# Sh3_Power.net
KiCad netlist of a schematic drawn in Altium Designer
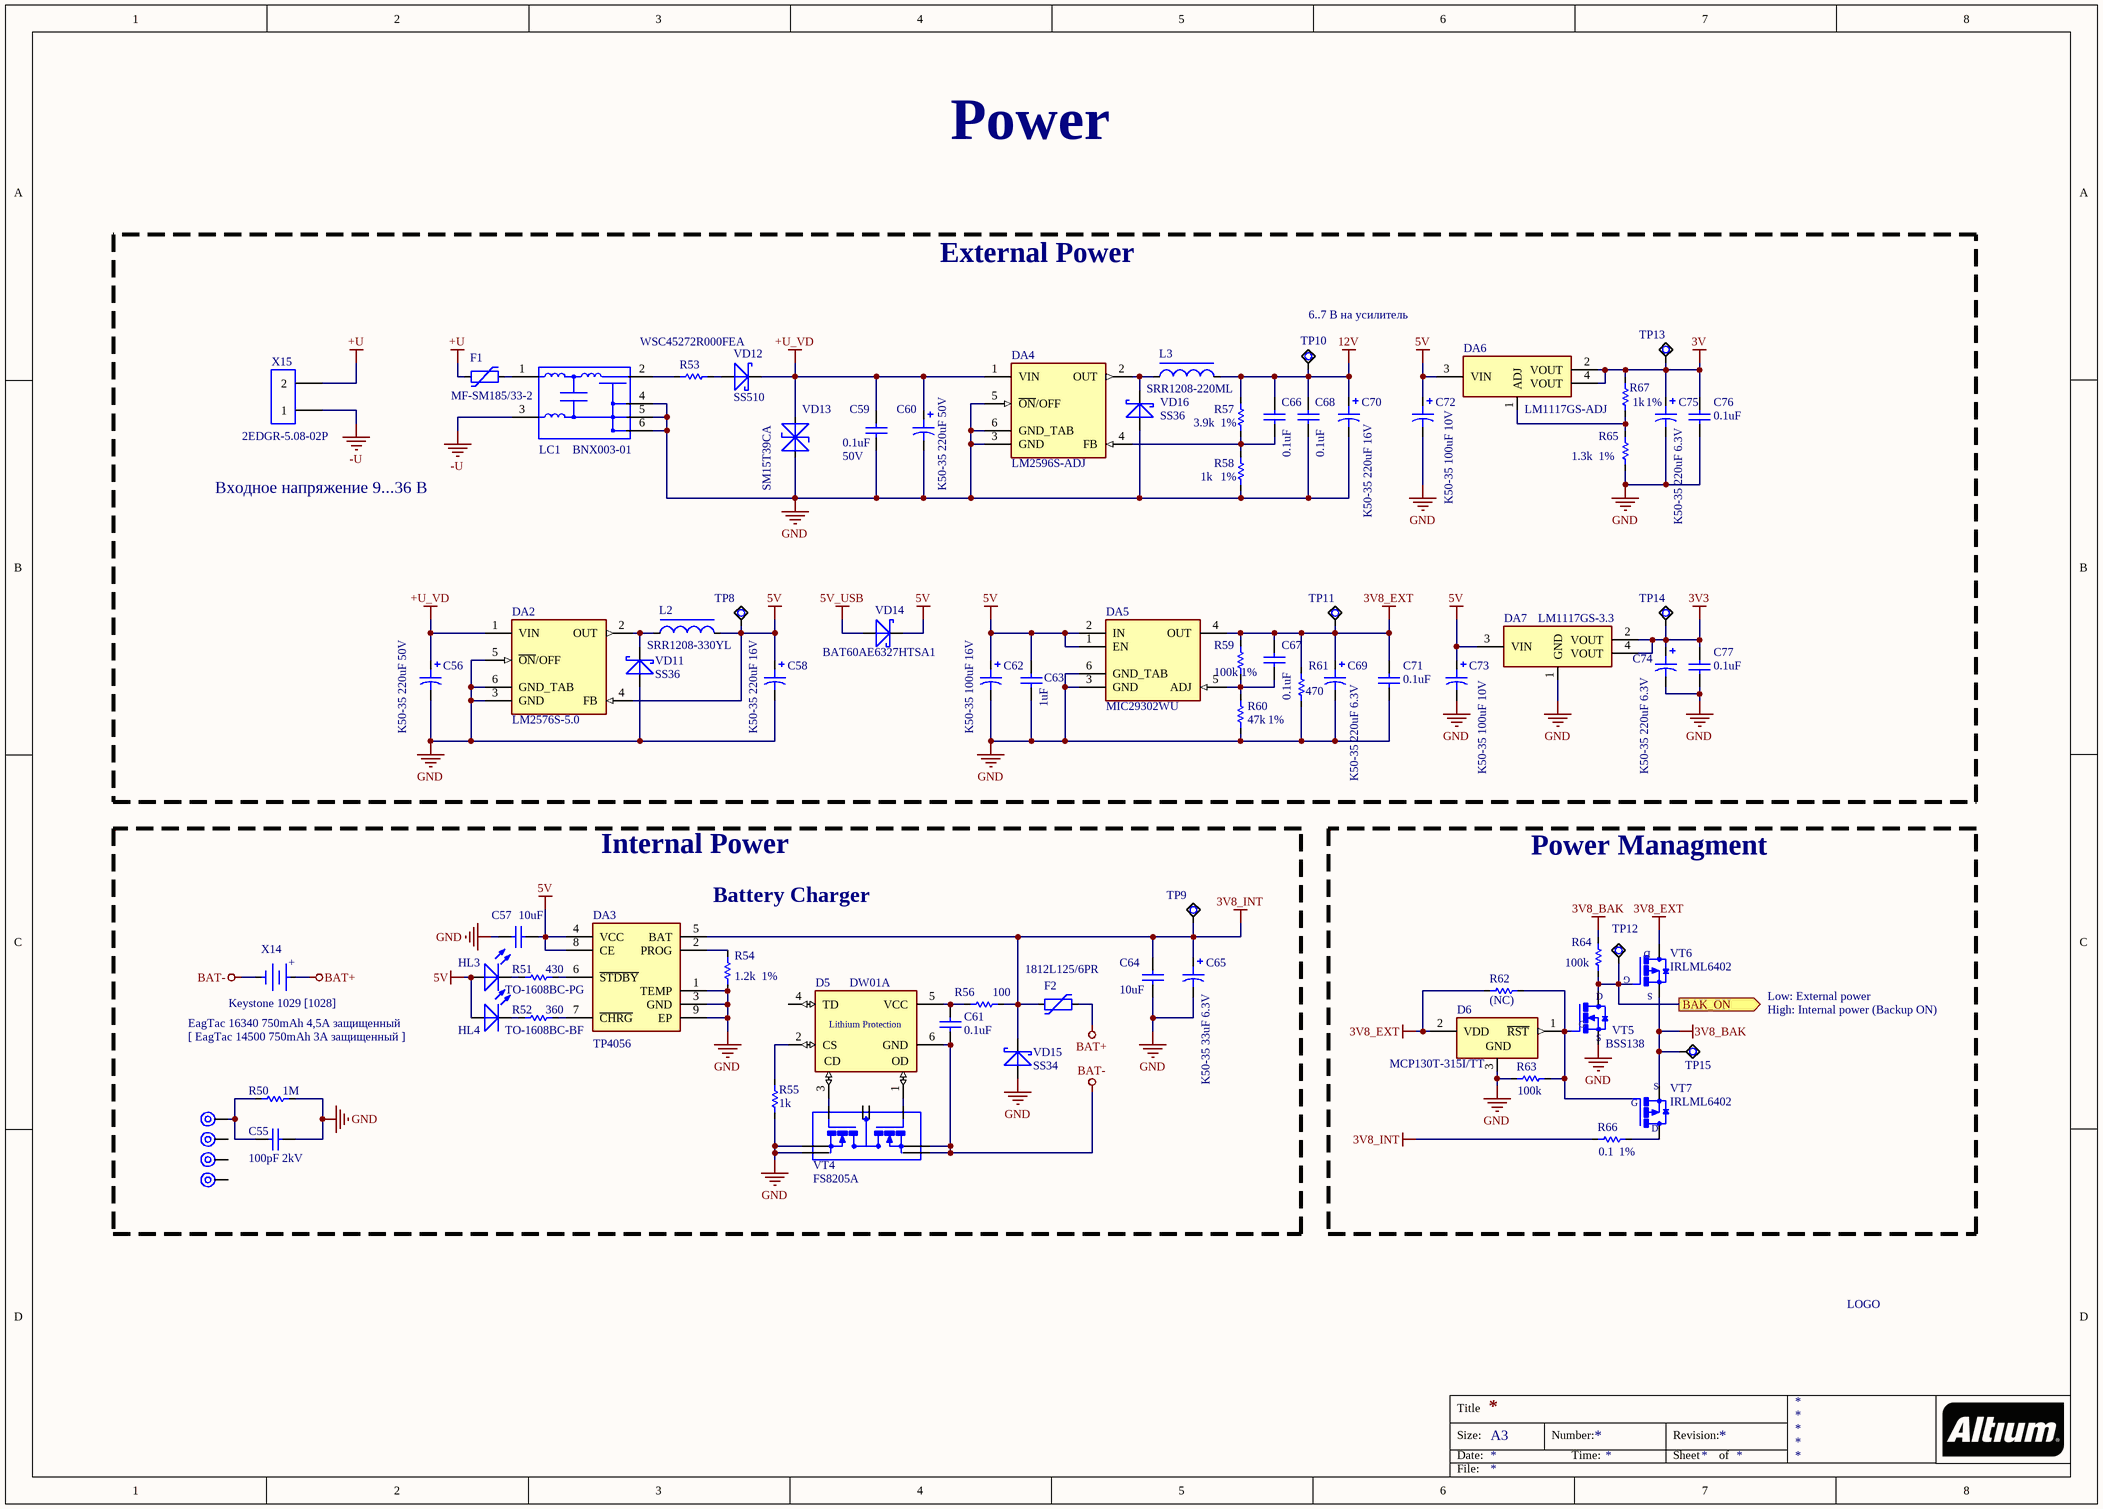
[diagram p0: Sh3_Power.SchDoc]

(export (version "E")
  (design (tool "Eeschema 10.0.6"))
  (components
    (comp (ref "BC1")
      (value "Mounting Hole")
      (footprint "body_connection_1")
      (libsource (lib "MyCompLib") (part "BodyConnector"))
    )
    (comp (ref "BC2")
      (value "Mounting Hole")
      (footprint "body_connection_1")
      (libsource (lib "MyCompLib") (part "BodyConnector"))
    )
    (comp (ref "BC3")
      (value "Mounting Hole")
      (footprint "body_connection_1")
      (libsource (lib "MyCompLib") (part "BodyConnector"))
    )
    (comp (ref "BC4")
      (value "Mounting Hole")
      (footprint "body_connection_1")
      (libsource (lib "MyCompLib") (part "BodyConnector"))
    )
    (comp (ref "C55")
      (value "100pF 2kV")
      (footprint "C_SMD1206")
      (description "1206 SMD Capacitor")
      (libsource (lib "MyCompLib") (part "C_SMD"))
    )
    (comp (ref "C56")
      (value "K50-35 220uF 50V")
      (footprint "K50-35 10x12.5x5")
      (description "Конденсатор электролитический алюминиевый")
      (libsource (lib "MyCompLib") (part "K50-35"))
    )
    (comp (ref "C57")
      (value "10uF")
      (footprint "C_SMD0603")
      (description "0603 SMD Capacitor")
      (libsource (lib "MyCompLib") (part "C_SMD"))
    )
    (comp (ref "C58")
      (value "K50-35 220uF 16V")
      (footprint "K50-35 6.3x11x2.5")
      (description "Конденсатор электролитический алюминиевый")
      (libsource (lib "MyCompLib") (part "K50-35"))
    )
    (comp (ref "C59")
      (value "0.1uF")
      (footprint "C_SMD0603")
      (description "0603 SMD Capacitor")
      (libsource (lib "MyCompLib") (part "C_SMD"))
    )
    (comp (ref "C60")
      (value "K50-35 220uF 50V")
      (footprint "K50-35 10x12.5x5")
      (description "Конденсатор электролитический алюминиевый")
      (libsource (lib "MyCompLib") (part "K50-35"))
    )
    (comp (ref "C61")
      (value "0.1uF")
      (footprint "C_SMD0603")
      (description "0603 SMD Capacitor")
      (libsource (lib "MyCompLib") (part "C_SMD"))
    )
    (comp (ref "C62")
      (value "K50-35 100uF 16V")
      (footprint "K50-35 6.3x11x2.5")
      (description "Конденсатор электролитический алюминиевый")
      (libsource (lib "MyCompLib") (part "K50-35"))
    )
    (comp (ref "C63")
      (value "1uF")
      (footprint "C_SMD0603")
      (description "0603 SMD Capacitor")
      (libsource (lib "MyCompLib") (part "C_SMD"))
    )
    (comp (ref "C64")
      (value "10uF")
      (footprint "C_SMD0603")
      (description "0603 SMD Capacitor")
      (libsource (lib "MyCompLib") (part "C_SMD"))
    )
    (comp (ref "C65")
      (value "K50-35 33uF 6.3V")
      (footprint "K50-35mini 4x7x2")
      (description "Конденсатор электролитический алюминиевый")
      (libsource (lib "MyCompLib") (part "K50-35"))
    )
    (comp (ref "C66")
      (value "0.1uF")
      (footprint "C_SMD0603")
      (description "0603 SMD Capacitor")
      (libsource (lib "MyCompLib") (part "C_SMD"))
    )
    (comp (ref "C67")
      (value "0.1uF")
      (footprint "C_SMD0603")
      (description "0603 SMD Capacitor")
      (libsource (lib "MyCompLib") (part "C_SMD"))
    )
    (comp (ref "C68")
      (value "0.1uF")
      (footprint "C_SMD0603")
      (description "0603 SMD Capacitor")
      (libsource (lib "MyCompLib") (part "C_SMD"))
    )
    (comp (ref "C69")
      (value "K50-35 220uF 6.3V")
      (footprint "K50-35 6.3x11x2.5")
      (description "Конденсатор электролитический алюминиевый")
      (libsource (lib "MyCompLib") (part "K50-35"))
    )
    (comp (ref "C70")
      (value "K50-35 220uF 16V")
      (footprint "K50-35 6.3x11x2.5")
      (description "Конденсатор электролитический алюминиевый")
      (libsource (lib "MyCompLib") (part "K50-35"))
    )
    (comp (ref "C71")
      (value "0.1uF")
      (footprint "C_SMD0603")
      (description "0603 SMD Capacitor")
      (libsource (lib "MyCompLib") (part "C_SMD"))
    )
    (comp (ref "C72")
      (value "K50-35 100uF 10V")
      (footprint "K50-35 5x11x2")
      (description "Конденсатор электролитический алюминиевый")
      (libsource (lib "MyCompLib") (part "K50-35"))
    )
    (comp (ref "C73")
      (value "K50-35 100uF 10V")
      (footprint "K50-35 5x11x2")
      (description "Конденсатор электролитический алюминиевый")
      (libsource (lib "MyCompLib") (part "K50-35"))
    )
    (comp (ref "C74")
      (value "K50-35 220uF 6.3V")
      (footprint "K50-35 6.3x11x2.5")
      (description "Конденсатор электролитический алюминиевый")
      (libsource (lib "MyCompLib") (part "K50-35"))
    )
    (comp (ref "C75")
      (value "K50-35 220uF 6.3V")
      (footprint "K50-35 6.3x11x2.5")
      (description "Конденсатор электролитический алюминиевый")
      (libsource (lib "MyCompLib") (part "K50-35"))
    )
    (comp (ref "C76")
      (value "0.1uF")
      (footprint "C_SMD0603")
      (description "0603 SMD Capacitor")
      (libsource (lib "MyCompLib") (part "C_SMD"))
    )
    (comp (ref "C77")
      (value "0.1uF")
      (footprint "C_SMD0603")
      (description "0603 SMD Capacitor")
      (libsource (lib "MyCompLib") (part "C_SMD"))
    )
    (comp (ref "D5")
      (value "DW01A")
      (footprint "SOT23-6-D")
      (description "Pushbutton Switch SPST-NC Standard Panel Mount, Front")
      (fields (field (name "MF") "Fortune Semiconductor"))
      (libsource (lib "MyCompLib") (part "DW01A"))
    )
    (comp (ref "D6")
      (value "MCP130T-315I/TT")
      (footprint "SOT23-3")
      (description "3.15 V 150 ms Microcontroller Supervisory Circuit - SOT-23-3")
      (fields (field (name "MF") "Microchip"))
      (libsource (lib "MyCompLib") (part "MCP130T-315I/TT"))
    )
    (comp (ref "DA2")
      (value "LM2576S-5.0")
      (footprint "TO263-5")
      (description "Импульсный понижающий регулятор напряжения, 5В, 3А, [TO-263]")
      (libsource (lib "MyCompLib") (part "LM2576S"))
    )
    (comp (ref "DA3")
      (value "TP4056")
      (footprint "SOIC127P600X175-9N")
      (description "Li-lon Battery Charger  1A Standalone Linear with Thermal Regulation in SOP-8")
      (libsource (lib "MyCompLib") (part "TP4056"))
    )
    (comp (ref "DA4")
      (value "LM2596S-ADJ")
      (footprint "TO263-5")
      (description "SIMPLE SWITCHER&#174; 4.5V to 40V, 3A Low Component Count Step-Down Regulator")
      (libsource (lib "MyCompLib") (part "LM2596S"))
    )
    (comp (ref "DA5")
      (value "MIC29302WU")
      (footprint "TO263-5 - heatsink")
      (libsource (lib "MyCompLib") (part "MIC29302WU"))
    )
    (comp (ref "DA6")
      (value "LM1117GS-ADJ")
      (footprint "SOT223")
      (libsource (lib "MyCompLib") (part "LM1117GS-ADJ"))
    )
    (comp (ref "DA7")
      (value "LM1117GS-3.3")
      (footprint "SOT223")
      (libsource (lib "MyCompLib") (part "LM1117GS-3.3"))
    )
    (comp (ref "F1")
      (value "MF-SM185/33-2")
      (footprint "FUSM8867X300N")
      (libsource (lib "MyCompLib") (part "MF-SM185/33-2"))
    )
    (comp (ref "F2")
      (value "1812L125/6PR")
      (footprint "FUSSC324X455X62L")
      (description "Предохранитель SMD 6 VDC 2.5 A")
      (libsource (lib "MyCompLib") (part "1812L125/6PR"))
    )
    (comp (ref "HL3")
      (value "TO-1608BC-PG")
      (footprint "LED_SMD1608GREEN")
      (description "Vf =2 V, 20mA, 0603\r\n\r\nTO-1608BC-BF \\  TO-1608BC-MRE")
      (libsource (lib "MyCompLib") (part "LED_SMD"))
    )
    (comp (ref "HL4")
      (value "TO-1608BC-BF")
      (footprint "LED_SMD1608")
      (description "Vf =2 V, 20mA, 0603\r\n\r\nTO-1608BC-BF \\  TO-1608BC-MRE")
      (libsource (lib "MyCompLib") (part "LED_SMD"))
    )
    (comp (ref "L2")
      (value "SRR1208-330YL")
      (footprint "SRR1208")
      (libsource (lib "MyCompLib") (part "SRR1208-330YL"))
    )
    (comp (ref "L3")
      (value "SRR1208-220ML")
      (footprint "SRR1208")
      (libsource (lib "MyCompLib") (part "SRR1208-330YL"))
    )
    (comp (ref "LC1")
      (value "BNX003-01")
      (footprint "Murata_BNX_L12MM5_W11MM5_T13MM0_MFG")
      (description "EMI фильтр индуктивно-емкостной 10A 150VDC 40дБ")
      (libsource (lib "MyCompLib") (part "BNX003-01"))
    )
    (comp (ref "N1")
      (value "Logo")
      (footprint "LOGO_SS")
      (description "Print on PCB mask")
      (libsource (lib "MyCompLib") (part "Logo"))
    )
    (comp (ref "R50")
      (value "1M")
      (footprint "R_SMD1206")
      (description "1206 SMD Resistor")
      (libsource (lib "MyCompLib") (part "R_SMD"))
    )
    (comp (ref "R51")
      (value "430")
      (footprint "R_SMD0603")
      (description "0603 SMD Resistor")
      (libsource (lib "MyCompLib") (part "R_SMD"))
    )
    (comp (ref "R52")
      (value "360")
      (footprint "R_SMD0603")
      (description "0603 SMD Resistor")
      (libsource (lib "MyCompLib") (part "R_SMD"))
    )
    (comp (ref "R53")
      (value "WSC45272R000FEA")
      (footprint "R_SMD4527")
      (description "SMD чип резистор, с проволочной обмоткой, 4527, 2 Ом, Серия WSC, 2 Вт")
      (libsource (lib "MyCompLib") (part "WSC45272R000FEA"))
    )
    (comp (ref "R54")
      (value "1.2k")
      (footprint "R_SMD0603")
      (description "0603 SMD Resistor 1%")
      (libsource (lib "MyCompLib") (part "R_SMD"))
    )
    (comp (ref "R55")
      (value "1k")
      (footprint "R_SMD0603")
      (description "0603 SMD Resistor")
      (libsource (lib "MyCompLib") (part "R_SMD"))
    )
    (comp (ref "R56")
      (value "100")
      (footprint "R_SMD0603")
      (description "0603 SMD Resistor")
      (libsource (lib "MyCompLib") (part "R_SMD"))
    )
    (comp (ref "R57")
      (value "3.9k")
      (footprint "R_SMD0603")
      (description "0603 SMD Resistor 1%")
      (libsource (lib "MyCompLib") (part "R_SMD"))
    )
    (comp (ref "R58")
      (value "1k")
      (footprint "R_SMD0603")
      (description "0603 SMD Resistor 1%")
      (libsource (lib "MyCompLib") (part "R_SMD"))
    )
    (comp (ref "R59")
      (value "100k")
      (footprint "R_SMD0603")
      (description "0603 SMD Resistor 1%")
      (libsource (lib "MyCompLib") (part "R_SMD"))
    )
    (comp (ref "R60")
      (value "47k")
      (footprint "R_SMD0603")
      (description "0603 SMD Resistor 1%")
      (libsource (lib "MyCompLib") (part "R_SMD"))
    )
    (comp (ref "R61")
      (value "470")
      (footprint "R_SMD0805")
      (description "0805 SMD Resistor")
      (libsource (lib "MyCompLib") (part "R_SMD"))
    )
    (comp (ref "R62")
      (value "(NC)")
      (footprint "R_SMD0603")
      (description "0603 SMD Resistor")
      (libsource (lib "MyCompLib") (part "R_SMD"))
    )
    (comp (ref "R63")
      (value "100k")
      (footprint "R_SMD0603")
      (description "0603 SMD Resistor")
      (libsource (lib "MyCompLib") (part "R_SMD"))
    )
    (comp (ref "R64")
      (value "100k")
      (footprint "R_SMD0603")
      (description "0603 SMD Resistor")
      (libsource (lib "MyCompLib") (part "R_SMD"))
    )
    (comp (ref "R65")
      (value "1.3k")
      (footprint "R_SMD0603")
      (description "0603 SMD Resistor 1%")
      (libsource (lib "MyCompLib") (part "R_SMD"))
    )
    (comp (ref "R66")
      (value "0.1")
      (footprint "R_SMD0805")
      (description "0805 SMD Resistor 1%")
      (libsource (lib "MyCompLib") (part "R_SMD"))
    )
    (comp (ref "R67")
      (value "1k")
      (footprint "R_SMD0603")
      (description "0603 SMD Resistor 1%")
      (libsource (lib "MyCompLib") (part "R_SMD"))
    )
    (comp (ref "TP8")
      (value "Test_point")
      (footprint "TEST_POINT")
      (description "Test point for PCB")
      (libsource (lib "MyCompLib") (part "Test_point"))
    )
    (comp (ref "TP9")
      (value "Test_point")
      (footprint "TEST_POINT")
      (description "Test point for PCB")
      (libsource (lib "MyCompLib") (part "Test_point"))
    )
    (comp (ref "TP10")
      (value "Test_point")
      (footprint "TEST_POINT")
      (description "Test point for PCB")
      (libsource (lib "MyCompLib") (part "Test_point"))
    )
    (comp (ref "TP11")
      (value "Test_point")
      (footprint "TEST_POINT")
      (description "Test point for PCB")
      (libsource (lib "MyCompLib") (part "Test_point"))
    )
    (comp (ref "TP12")
      (value "Test_point")
      (footprint "TEST_POINT")
      (description "Test point for PCB")
      (libsource (lib "MyCompLib") (part "Test_point"))
    )
    (comp (ref "TP13")
      (value "Test_point")
      (footprint "TEST_POINT")
      (description "Test point for PCB")
      (libsource (lib "MyCompLib") (part "Test_point"))
    )
    (comp (ref "TP14")
      (value "Test_point")
      (footprint "TEST_POINT")
      (description "Test point for PCB")
      (libsource (lib "MyCompLib") (part "Test_point"))
    )
    (comp (ref "TP15")
      (value "Test_point")
      (footprint "TEST_POINT")
      (description "Test point for PCB")
      (libsource (lib "MyCompLib") (part "Test_point"))
    )
    (comp (ref "VD11")
      (value "SS36")
      (footprint "DO214AB SMC")
      (description "Schottky; DO-214AB; 3.0A IF; 0.75V; 60V; 100A IFRM; 10000V/us; 1000pF")
      (libsource (lib "MyCompLib") (part "SS36"))
    )
    (comp (ref "VD12")
      (value "SS510")
      (footprint "SMC")
      (description "Диод Шоттки 5A 100V (SMC)")
      (libsource (lib "MyCompLib") (part "SS510"))
    )
    (comp (ref "VD13")
      (value "SM15T39CA")
      (footprint "DO214AB SMC")
      (description "TVS Diode Bi-Directional SM15T39CA 69.7V, 1500W, SMC 2-Pin")
      (libsource (lib "MyCompLib") (part "SM15T39CA"))
    )
    (comp (ref "VD14")
      (value "BAT60AE6327HTSA1")
      (footprint "SOD-323")
      (description "Диод Шоттки 3А 10В [SOD-323]")
      (libsource (lib "MyCompLib") (part "BAT60AE6327HTSA1"))
    )
    (comp (ref "VD15")
      (value "SS34")
      (footprint "DO214AB SMC")
      (description "Schottky; DO-214AB; 3.0A IF; 0.75V; 40V; 100A IFRM; 10000V/us; 1000pF")
      (libsource (lib "MyCompLib") (part "SS34"))
    )
    (comp (ref "VD16")
      (value "SS36")
      (footprint "DO214AB SMC")
      (description "Schottky; DO-214AB; 3.0A IF; 0.75V; 60V; 100A IFRM; 10000V/us; 1000pF")
      (libsource (lib "MyCompLib") (part "SS36"))
    )
    (comp (ref "VT4")
      (value "FS8205A")
      (footprint "SOP65P640X120-8N")
      (description "20V 6A DUAL N-Channel MOSFET Transistor")
      (libsource (lib "MyCompLib") (part "FS8205A"))
    )
    (comp (ref "VT5")
      (value "BSS138")
      (footprint "SOT23-3")
      (description "MOSFET, N-канал, 0.2А, 50В, [SOT-23]")
      (libsource (lib "MyCompLib") (part "BSS138"))
    )
    (comp (ref "VT6")
      (value "IRLML6402")
      (footprint "SOT23")
      (description "P-Channel 20V 3.7A _Ta_ 1.3W _Ta_ Surface Mount/SOT-23")
      (fields (field (name "MF") "Infineon Technologies"))
      (libsource (lib "MyCompLib") (part "IRLML6402"))
    )
    (comp (ref "VT7")
      (value "IRLML6402")
      (footprint "SOT23")
      (description "P-Channel 20V 3.7A _Ta_ 1.3W _Ta_ Surface Mount/SOT-23")
      (fields (field (name "MF") "Infineon Technologies"))
      (libsource (lib "") (part "IRLML6402_1"))
    )
    (comp (ref "X14")
      (value "Keystone 1029 [1028]")
      (footprint "BAT_keystone1028+1029")
      (description "16340 2/3A [14500 AA] Battery Holder")
      (libsource (lib "MyCompLib") (part "Combo Battery Holder"))
    )
    (comp (ref "X15")
      (value "2EDGR-5.08-02P")
      (footprint "2EDGR-5.08-02P")
      (libsource (lib "MyCompLib") (part "2EDGR-5.08-02P"))
    )
  )
  (nets
    (net (code "1") (name "+U") (class "Default")
      (node (ref "F1") (pin "1") (pinfunction "1_1") (pintype "passive"))
      (node (ref "X15") (pin "2") (pinfunction "2_2") (pintype "passive"))
    )
    (net (code "2") (name "+U_VD") (class "Default")
      (node (ref "C56") (pin "1") (pinfunction "1_1") (pintype "passive"))
      (node (ref "C59") (pin "1") (pinfunction "1_1") (pintype "passive"))
      (node (ref "C60") (pin "1") (pinfunction "1_1") (pintype "passive"))
      (node (ref "DA2") (pin "1") (pinfunction "VIN_1") (pintype "power_in"))
      (node (ref "DA4") (pin "1") (pinfunction "VIN_1") (pintype "power_in"))
      (node (ref "VD12") (pin "C") (pinfunction "NEG_C") (pintype "passive"))
      (node (ref "VD13") (pin "2") (pinfunction "K_2") (pintype "passive"))
    )
    (net (code "3") (name "-U") (class "Default")
      (node (ref "LC1") (pin "3") (pinfunction "PSG_3") (pintype "passive"))
      (node (ref "X15") (pin "1") (pinfunction "1_1") (pintype "passive"))
    )
    (net (code "4") (name "/BAK_ON") (class "Default")
      (node (ref "R64") (pin "2") (pinfunction "CW_2") (pintype "passive"))
      (node (ref "TP12") (pin "1") (pinfunction "1_1") (pintype "passive"))
      (node (ref "VT5") (pin "3") (pinfunction "D_3") (pintype "passive"))
      (node (ref "VT6") (pin "1") (pinfunction "G_1") (pintype "passive"))
    )
    (net (code "5") (name "3V") (class "Default")
      (node (ref "C75") (pin "1") (pinfunction "1_1") (pintype "passive"))
      (node (ref "C76") (pin "1") (pinfunction "1_1") (pintype "passive"))
      (node (ref "DA6") (pin "2") (pinfunction "VOUT_2") (pintype "power_in"))
      (node (ref "DA6") (pin "4") (pinfunction "VOUT_4") (pintype "power_in"))
      (node (ref "R67") (pin "2") (pinfunction "CW_2") (pintype "passive"))
      (node (ref "TP13") (pin "1") (pinfunction "1_1") (pintype "passive"))
    )
    (net (code "6") (name "3V3") (class "Default")
      (node (ref "C74") (pin "1") (pinfunction "1_1") (pintype "passive"))
      (node (ref "C77") (pin "1") (pinfunction "1_1") (pintype "passive"))
      (node (ref "DA7") (pin "2") (pinfunction "VOUT_2") (pintype "power_in"))
      (node (ref "DA7") (pin "4") (pinfunction "VOUT_4") (pintype "power_in"))
      (node (ref "TP14") (pin "1") (pinfunction "1_1") (pintype "passive"))
    )
    (net (code "7") (name "3V8_BAK") (class "Default")
      (node (ref "R64") (pin "1") (pinfunction "CCW_1") (pintype "passive"))
      (node (ref "TP15") (pin "1") (pinfunction "1_1") (pintype "passive"))
      (node (ref "VT6") (pin "2") (pinfunction "S_2") (pintype "passive"))
      (node (ref "VT7") (pin "2") (pinfunction "S_2") (pintype "passive"))
    )
    (net (code "8") (name "3V8_EXT") (class "Default")
      (node (ref "C67") (pin "1") (pinfunction "1_1") (pintype "passive"))
      (node (ref "C69") (pin "1") (pinfunction "1_1") (pintype "passive"))
      (node (ref "C71") (pin "1") (pinfunction "1_1") (pintype "passive"))
      (node (ref "D6") (pin "2") (pinfunction "VDD_2") (pintype "power_in"))
      (node (ref "DA5") (pin "4") (pinfunction "OUT_4") (pintype "power_in"))
      (node (ref "R59") (pin "2") (pinfunction "CW_2") (pintype "passive"))
      (node (ref "R61") (pin "2") (pinfunction "CW_2") (pintype "passive"))
      (node (ref "R62") (pin "2") (pinfunction "CW_2") (pintype "passive"))
      (node (ref "TP11") (pin "1") (pinfunction "1_1") (pintype "passive"))
      (node (ref "VT6") (pin "3") (pinfunction "D_3") (pintype "passive"))
    )
    (net (code "9") (name "3V8_INT") (class "Default")
      (node (ref "C64") (pin "1") (pinfunction "1_1") (pintype "passive"))
      (node (ref "C65") (pin "1") (pinfunction "1_1") (pintype "passive"))
      (node (ref "DA3") (pin "5") (pinfunction "BAT_5") (pintype "passive"))
      (node (ref "F2") (pin "1") (pinfunction "1_1") (pintype "passive"))
      (node (ref "R56") (pin "1") (pinfunction "CCW_1") (pintype "passive"))
      (node (ref "R66") (pin "2") (pinfunction "CW_2") (pintype "passive"))
      (node (ref "TP9") (pin "1") (pinfunction "1_1") (pintype "passive"))
      (node (ref "VD15") (pin "2") (pinfunction "NEG_2") (pintype "passive"))
    )
    (net (code "10") (name "5V") (class "Default")
      (node (ref "C57") (pin "2") (pinfunction "2_2") (pintype "passive"))
      (node (ref "C58") (pin "1") (pinfunction "1_1") (pintype "passive"))
      (node (ref "C62") (pin "1") (pinfunction "1_1") (pintype "passive"))
      (node (ref "C63") (pin "1") (pinfunction "1_1") (pintype "passive"))
      (node (ref "C72") (pin "1") (pinfunction "1_1") (pintype "passive"))
      (node (ref "C73") (pin "1") (pinfunction "1_1") (pintype "passive"))
      (node (ref "DA2") (pin "4") (pinfunction "FB_4") (pintype "input"))
      (node (ref "DA3") (pin "4") (pinfunction "VCC_4") (pintype "passive"))
      (node (ref "DA3") (pin "8") (pinfunction "CE_8") (pintype "passive"))
      (node (ref "DA5") (pin "1") (pinfunction "EN_1") (pintype "power_in"))
      (node (ref "DA5") (pin "2") (pinfunction "IN_2") (pintype "power_in"))
      (node (ref "DA6") (pin "3") (pinfunction "VIN_3") (pintype "power_in"))
      (node (ref "DA7") (pin "3") (pinfunction "VIN_3") (pintype "power_in"))
      (node (ref "HL3") (pin "1") (pinfunction "POS_1") (pintype "passive"))
      (node (ref "HL4") (pin "1") (pinfunction "POS_1") (pintype "passive"))
      (node (ref "L2") (pin "2") (pinfunction "2_2") (pintype "passive"))
      (node (ref "TP8") (pin "1") (pinfunction "1_1") (pintype "passive"))
      (node (ref "VD14") (pin "2") (pinfunction "NEG_2") (pintype "passive"))
    )
    (net (code "11") (name "5V_USB") (class "Default")
      (node (ref "VD14") (pin "1") (pinfunction "POS_1") (pintype "passive"))
    )
    (net (code "12") (name "12V") (class "Default")
      (node (ref "C66") (pin "1") (pinfunction "1_1") (pintype "passive"))
      (node (ref "C68") (pin "1") (pinfunction "1_1") (pintype "passive"))
      (node (ref "C70") (pin "1") (pinfunction "1_1") (pintype "passive"))
      (node (ref "L3") (pin "2") (pinfunction "2_2") (pintype "passive"))
      (node (ref "R57") (pin "2") (pinfunction "CW_2") (pintype "passive"))
      (node (ref "TP10") (pin "1") (pinfunction "1_1") (pintype "passive"))
    )
    (net (code "13") (name "BAT+") (class "Default")
      (node (ref "F2") (pin "2") (pinfunction "2_2") (pintype "passive"))
      (node (ref "X14") (pin "POS") (pinfunction "POS_POS") (pintype "passive"))
    )
    (net (code "14") (name "BAT-") (class "Default")
      (node (ref "C61") (pin "2") (pinfunction "2_2") (pintype "passive"))
      (node (ref "D5") (pin "6") (pinfunction "GND_6") (pintype "power_in"))
      (node (ref "VT4") (pin "2") (pinfunction "S1_1_2") (pintype "passive"))
      (node (ref "VT4") (pin "3") (pinfunction "S1_2_3") (pintype "passive"))
      (node (ref "X14") (pin "NEG") (pinfunction "NEG_NEG") (pintype "passive"))
    )
    (net (code "15") (name "GND") (class "Default")
      (node (ref "C55") (pin "2") (pinfunction "2_2") (pintype "passive"))
      (node (ref "C56") (pin "2") (pinfunction "2_2") (pintype "passive"))
      (node (ref "C57") (pin "1") (pinfunction "1_1") (pintype "passive"))
      (node (ref "C58") (pin "2") (pinfunction "2_2") (pintype "passive"))
      (node (ref "C59") (pin "2") (pinfunction "2_2") (pintype "passive"))
      (node (ref "C60") (pin "2") (pinfunction "2_2") (pintype "passive"))
      (node (ref "C62") (pin "2") (pinfunction "2_2") (pintype "passive"))
      (node (ref "C63") (pin "2") (pinfunction "2_2") (pintype "passive"))
      (node (ref "C64") (pin "2") (pinfunction "2_2") (pintype "passive"))
      (node (ref "C65") (pin "2") (pinfunction "2_2") (pintype "passive"))
      (node (ref "C68") (pin "2") (pinfunction "2_2") (pintype "passive"))
      (node (ref "C69") (pin "2") (pinfunction "2_2") (pintype "passive"))
      (node (ref "C70") (pin "2") (pinfunction "2_2") (pintype "passive"))
      (node (ref "C71") (pin "2") (pinfunction "2_2") (pintype "passive"))
      (node (ref "C72") (pin "2") (pinfunction "2_2") (pintype "passive"))
      (node (ref "C73") (pin "2") (pinfunction "2_2") (pintype "passive"))
      (node (ref "C74") (pin "2") (pinfunction "2_2") (pintype "passive"))
      (node (ref "C75") (pin "2") (pinfunction "2_2") (pintype "passive"))
      (node (ref "C76") (pin "2") (pinfunction "2_2") (pintype "passive"))
      (node (ref "C77") (pin "2") (pinfunction "2_2") (pintype "passive"))
      (node (ref "D6") (pin "3") (pinfunction "VSS_3") (pintype "power_in"))
      (node (ref "DA2") (pin "3") (pinfunction "GND_3") (pintype "passive"))
      (node (ref "DA2") (pin "5") (pinfunction "~{ON}/OFF_5") (pintype "input"))
      (node (ref "DA2") (pin "6") (pinfunction "GND_TAB_6") (pintype "passive"))
      (node (ref "DA3") (pin "1") (pinfunction "TEMP_1") (pintype "passive"))
      (node (ref "DA3") (pin "3") (pinfunction "GND_3") (pintype "passive"))
      (node (ref "DA3") (pin "9") (pinfunction "EP_9") (pintype "passive"))
      (node (ref "DA4") (pin "3") (pinfunction "GND_3") (pintype "passive"))
      (node (ref "DA4") (pin "5") (pinfunction "~{ON}/OFF_5") (pintype "input"))
      (node (ref "DA4") (pin "6") (pinfunction "GND_TAB_6") (pintype "passive"))
      (node (ref "DA5") (pin "3") (pinfunction "GND_3") (pintype "passive"))
      (node (ref "DA5") (pin "6") (pinfunction "GND_TAB_6") (pintype "passive"))
      (node (ref "DA7") (pin "1") (pinfunction "GND_1") (pintype "passive"))
      (node (ref "LC1") (pin "4") (pinfunction "CG_4") (pintype "passive"))
      (node (ref "LC1") (pin "5") (pinfunction "CG_5") (pintype "passive"))
      (node (ref "LC1") (pin "6") (pinfunction "CG_6") (pintype "passive"))
      (node (ref "R50") (pin "2") (pinfunction "CW_2") (pintype "passive"))
      (node (ref "R54") (pin "1") (pinfunction "CCW_1") (pintype "passive"))
      (node (ref "R55") (pin "2") (pinfunction "CW_2") (pintype "passive"))
      (node (ref "R58") (pin "1") (pinfunction "CCW_1") (pintype "passive"))
      (node (ref "R60") (pin "1") (pinfunction "CCW_1") (pintype "passive"))
      (node (ref "R61") (pin "1") (pinfunction "CCW_1") (pintype "passive"))
      (node (ref "R63") (pin "2") (pinfunction "CW_2") (pintype "passive"))
      (node (ref "R65") (pin "1") (pinfunction "CCW_1") (pintype "passive"))
      (node (ref "VD11") (pin "1") (pinfunction "POS_1") (pintype "passive"))
      (node (ref "VD13") (pin "1") (pinfunction "A_1") (pintype "passive"))
      (node (ref "VD15") (pin "1") (pinfunction "POS_1") (pintype "passive"))
      (node (ref "VD16") (pin "1") (pinfunction "POS_1") (pintype "passive"))
      (node (ref "VT4") (pin "6") (pinfunction "S2_1_6") (pintype "passive"))
      (node (ref "VT4") (pin "7") (pinfunction "S2_2_7") (pintype "passive"))
      (node (ref "VT5") (pin "2") (pinfunction "S_2") (pintype "passive"))
    )
    (net (code "16") (name "Net-(D5-CS)") (class "Default")
      (node (ref "D5") (pin "2") (pinfunction "CS_2") (pintype "bidirectional"))
      (node (ref "R55") (pin "1") (pinfunction "CCW_1") (pintype "passive"))
    )
    (net (code "17") (name "Net-(D5-OC)") (class "Default")
      (node (ref "D5") (pin "3") (pinfunction "OC_3") (pintype "bidirectional"))
      (node (ref "VT4") (pin "5") (pinfunction "G2_5") (pintype "passive"))
    )
    (net (code "18") (name "Net-(D5-OD)") (class "Default")
      (node (ref "D5") (pin "1") (pinfunction "OD_1") (pintype "bidirectional"))
      (node (ref "VT4") (pin "4") (pinfunction "G1_4") (pintype "passive"))
    )
    (net (code "19") (name "Net-(D5-VCC)") (class "Default")
      (node (ref "C61") (pin "1") (pinfunction "1_1") (pintype "passive"))
      (node (ref "D5") (pin "5") (pinfunction "VCC_5") (pintype "power_in"))
      (node (ref "R56") (pin "2") (pinfunction "CW_2") (pintype "passive"))
    )
    (net (code "20") (name "Net-(D6-~{RST})") (class "Default")
      (node (ref "D6") (pin "1") (pinfunction "~{RST}_1") (pintype "output"))
      (node (ref "R62") (pin "1") (pinfunction "CCW_1") (pintype "passive"))
      (node (ref "R63") (pin "1") (pinfunction "CCW_1") (pintype "passive"))
      (node (ref "VT5") (pin "1") (pinfunction "G_1") (pintype "passive"))
      (node (ref "VT7") (pin "1") (pinfunction "G_1") (pintype "passive"))
    )
    (net (code "21") (name "Net-(DA2-OUT)") (class "Default")
      (node (ref "DA2") (pin "2") (pinfunction "OUT_2") (pintype "output"))
      (node (ref "L2") (pin "1") (pinfunction "1_1") (pintype "passive"))
      (node (ref "VD11") (pin "2") (pinfunction "NEG_2") (pintype "passive"))
    )
    (net (code "22") (name "Net-(DA3-PROG)") (class "Default")
      (node (ref "DA3") (pin "2") (pinfunction "PROG_2") (pintype "passive"))
      (node (ref "R54") (pin "2") (pinfunction "CW_2") (pintype "passive"))
    )
    (net (code "23") (name "Net-(DA3-~{CHRG})") (class "Default")
      (node (ref "DA3") (pin "7") (pinfunction "~{CHRG}_7") (pintype "passive"))
      (node (ref "R52") (pin "1") (pinfunction "CCW_1") (pintype "passive"))
    )
    (net (code "24") (name "Net-(DA3-~{STDBY})") (class "Default")
      (node (ref "DA3") (pin "6") (pinfunction "~{STDBY}_6") (pintype "passive"))
      (node (ref "R51") (pin "1") (pinfunction "CCW_1") (pintype "passive"))
    )
    (net (code "25") (name "Net-(DA4-FB)") (class "Default")
      (node (ref "C66") (pin "2") (pinfunction "2_2") (pintype "passive"))
      (node (ref "DA4") (pin "4") (pinfunction "FB_4") (pintype "input"))
      (node (ref "R57") (pin "1") (pinfunction "CCW_1") (pintype "passive"))
      (node (ref "R58") (pin "2") (pinfunction "CW_2") (pintype "passive"))
    )
    (net (code "26") (name "Net-(DA4-OUT)") (class "Default")
      (node (ref "DA4") (pin "2") (pinfunction "OUT_2") (pintype "output"))
      (node (ref "L3") (pin "1") (pinfunction "1_1") (pintype "passive"))
      (node (ref "VD16") (pin "2") (pinfunction "NEG_2") (pintype "passive"))
    )
    (net (code "27") (name "Net-(DA5-ADJ)") (class "Default")
      (node (ref "C67") (pin "2") (pinfunction "2_2") (pintype "passive"))
      (node (ref "DA5") (pin "5") (pinfunction "ADJ_5") (pintype "input"))
      (node (ref "R59") (pin "1") (pinfunction "CCW_1") (pintype "passive"))
      (node (ref "R60") (pin "2") (pinfunction "CW_2") (pintype "passive"))
    )
    (net (code "28") (name "Net-(DA6-ADJ)") (class "Default")
      (node (ref "DA6") (pin "1") (pinfunction "ADJ_1") (pintype "passive"))
      (node (ref "R65") (pin "2") (pinfunction "CW_2") (pintype "passive"))
      (node (ref "R67") (pin "1") (pinfunction "CCW_1") (pintype "passive"))
    )
    (net (code "29") (name "Net-(HL3-NEG)") (class "Default")
      (node (ref "HL3") (pin "2") (pinfunction "NEG_2") (pintype "passive"))
      (node (ref "R51") (pin "2") (pinfunction "CW_2") (pintype "passive"))
    )
    (net (code "30") (name "Net-(HL4-NEG)") (class "Default")
      (node (ref "HL4") (pin "2") (pinfunction "NEG_2") (pintype "passive"))
      (node (ref "R52") (pin "2") (pinfunction "CW_2") (pintype "passive"))
    )
    (net (code "31") (name "Net-(LC1-B)") (class "Default")
      (node (ref "F1") (pin "2") (pinfunction "2_2") (pintype "passive"))
      (node (ref "LC1") (pin "1") (pinfunction "B_1") (pintype "passive"))
    )
    (net (code "32") (name "Net-(LC1-CB)") (class "Default")
      (node (ref "LC1") (pin "2") (pinfunction "CB_2") (pintype "passive"))
      (node (ref "R53") (pin "1") (pinfunction "CCW_1") (pintype "passive"))
    )
    (net (code "33") (name "Net-(R50-CCW)") (class "Default")
      (node (ref "BC1") (pin "1") (pinfunction "1_1") (pintype "passive"))
      (node (ref "C55") (pin "1") (pinfunction "1_1") (pintype "passive"))
      (node (ref "R50") (pin "1") (pinfunction "CCW_1") (pintype "passive"))
    )
    (net (code "34") (name "Net-(R53-CW)") (class "Default")
      (node (ref "R53") (pin "2") (pinfunction "CW_2") (pintype "passive"))
      (node (ref "VD12") (pin "A") (pinfunction "POS_A") (pintype "passive"))
    )
    (net (code "35") (name "Net-(R66-CCW)") (class "Default")
      (node (ref "R66") (pin "1") (pinfunction "CCW_1") (pintype "passive"))
      (node (ref "VT7") (pin "3") (pinfunction "D_3") (pintype "passive"))
    )
    (net (code "36") (name "unconnected-(BC2-Pad1)") (class "Default")
      (node (ref "BC2") (pin "1") (pinfunction "1_1") (pintype "passive"))
    )
    (net (code "37") (name "unconnected-(BC3-Pad1)") (class "Default")
      (node (ref "BC3") (pin "1") (pinfunction "1_1") (pintype "passive"))
    )
    (net (code "38") (name "unconnected-(BC4-Pad1)") (class "Default")
      (node (ref "BC4") (pin "1") (pinfunction "1_1") (pintype "passive"))
    )
    (net (code "39") (name "unconnected-(D5-TD-Pad4)") (class "Default")
      (node (ref "D5") (pin "4") (pinfunction "TD_4") (pintype "bidirectional"))
    )
    (net (code "40") (name "unconnected-(VT4-D12_1-Pad1)") (class "Default")
      (node (ref "VT4") (pin "1") (pinfunction "D12_1_1") (pintype "passive"))
    )
    (net (code "41") (name "unconnected-(VT4-D12_2-Pad8)") (class "Default")
      (node (ref "VT4") (pin "8") (pinfunction "D12_2_8") (pintype "passive"))
    )
  )
)
